# dcc-monitor.net
KiCad netlist of a schematic drawn in EAGLE
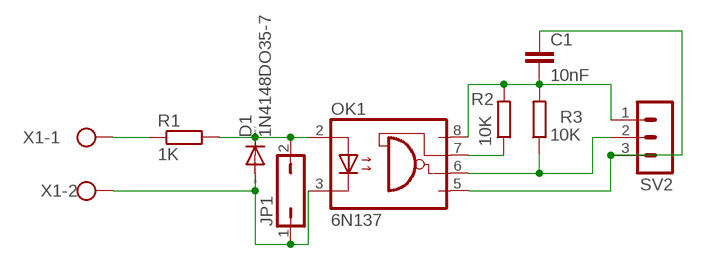
[diagram p0: schematic, sheet 1]

(export (version "E")
  (design (tool "Eeschema 10.0.6"))
  (components
    (comp (ref "C1")
      (value "10nF")
      (footprint "eagle-import:C025-025X050")
      (libsource (lib "eagle-import") (part "C-EU025-025X050"))
    )
    (comp (ref "D1")
      (value "1N4148DO35-7")
      (footprint "eagle-import:DO35-7")
      (libsource (lib "eagle-import") (part "1N4148DO35-7"))
    )
    (comp (ref "JP1")
      (value "JP1Q")
      (footprint "eagle-import:JP1")
      (libsource (lib "eagle-import") (part "JP1Q"))
    )
    (comp (ref "OK1")
      (value "6N137")
      (footprint "eagle-import:DIL08")
      (libsource (lib "eagle-import") (part "6N137"))
    )
    (comp (ref "R1")
      (value "1K")
      (footprint "eagle-import:0309_12")
      (libsource (lib "eagle-import") (part "R-EU_0309/12"))
    )
    (comp (ref "R2")
      (value "10K")
      (footprint "eagle-import:0309_12")
      (libsource (lib "eagle-import") (part "R-EU_0309/12"))
    )
    (comp (ref "R3")
      (value "10K")
      (footprint "eagle-import:0309_12")
      (libsource (lib "eagle-import") (part "R-EU_0309/12"))
    )
    (comp (ref "SV2")
      (value "MA03-1")
      (footprint "eagle-import:MA03-1")
      (libsource (lib "eagle-import") (part "MA03-1"))
    )
    (comp (ref "X1")
      (value "W237-102")
      (footprint "eagle-import:W237-102")
      (fields (field (name "MPN") "237-102"))
      (libsource (lib "eagle-import") (part "W237-102"))
    )
  )
  (nets
    (net (code "1") (name "Net-(OK1-A)") (class "Default")
      (node (ref "D1") (pin "C") (pinfunction "C_C") (pintype "passive"))
      (node (ref "JP1") (pin "2") (pinfunction "2_2") (pintype "passive"))
      (node (ref "OK1") (pin "2") (pinfunction "A_2") (pintype "passive"))
      (node (ref "R1") (pin "2") (pinfunction "2_2") (pintype "passive"))
    )
    (net (code "2") (name "Net-(OK1-C)") (class "Default")
      (node (ref "D1") (pin "A") (pinfunction "A_A") (pintype "passive"))
      (node (ref "JP1") (pin "1") (pinfunction "1_1") (pintype "passive"))
      (node (ref "OK1") (pin "3") (pinfunction "C_3") (pintype "passive"))
      (node (ref "X1") (pin "2") (pinfunction "KL_2") (pintype "passive"))
    )
    (net (code "3") (name "Net-(OK1-GND)") (class "Default")
      (node (ref "C1") (pin "1") (pinfunction "1_1") (pintype "passive"))
      (node (ref "OK1") (pin "5") (pinfunction "GND_5") (pintype "passive"))
      (node (ref "SV2") (pin "3") (pinfunction "3_3") (pintype "passive"))
    )
    (net (code "4") (name "Net-(OK1-VCC)") (class "Default")
      (node (ref "C1") (pin "2") (pinfunction "2_2") (pintype "passive"))
      (node (ref "OK1") (pin "8") (pinfunction "VCC_8") (pintype "passive"))
      (node (ref "R2") (pin "2") (pinfunction "2_2") (pintype "passive"))
      (node (ref "R3") (pin "2") (pinfunction "2_2") (pintype "passive"))
      (node (ref "SV2") (pin "1") (pinfunction "1_1") (pintype "passive"))
    )
    (net (code "5") (name "Net-(OK1-VE)") (class "Default")
      (node (ref "OK1") (pin "7") (pinfunction "VE_7") (pintype "passive"))
      (node (ref "R2") (pin "1") (pinfunction "1_1") (pintype "passive"))
    )
    (net (code "6") (name "Net-(OK1-VO)") (class "Default")
      (node (ref "OK1") (pin "6") (pinfunction "VO_6") (pintype "passive"))
      (node (ref "R3") (pin "1") (pinfunction "1_1") (pintype "passive"))
      (node (ref "SV2") (pin "2") (pinfunction "2_2") (pintype "passive"))
    )
    (net (code "7") (name "Net-(X1A-KL)") (class "Default")
      (node (ref "R1") (pin "1") (pinfunction "1_1") (pintype "passive"))
      (node (ref "X1") (pin "1") (pinfunction "KL_1") (pintype "passive"))
    )
  )
)
